# PDB_schem.net
KiCad netlist of a schematic drawn in Altium Designer
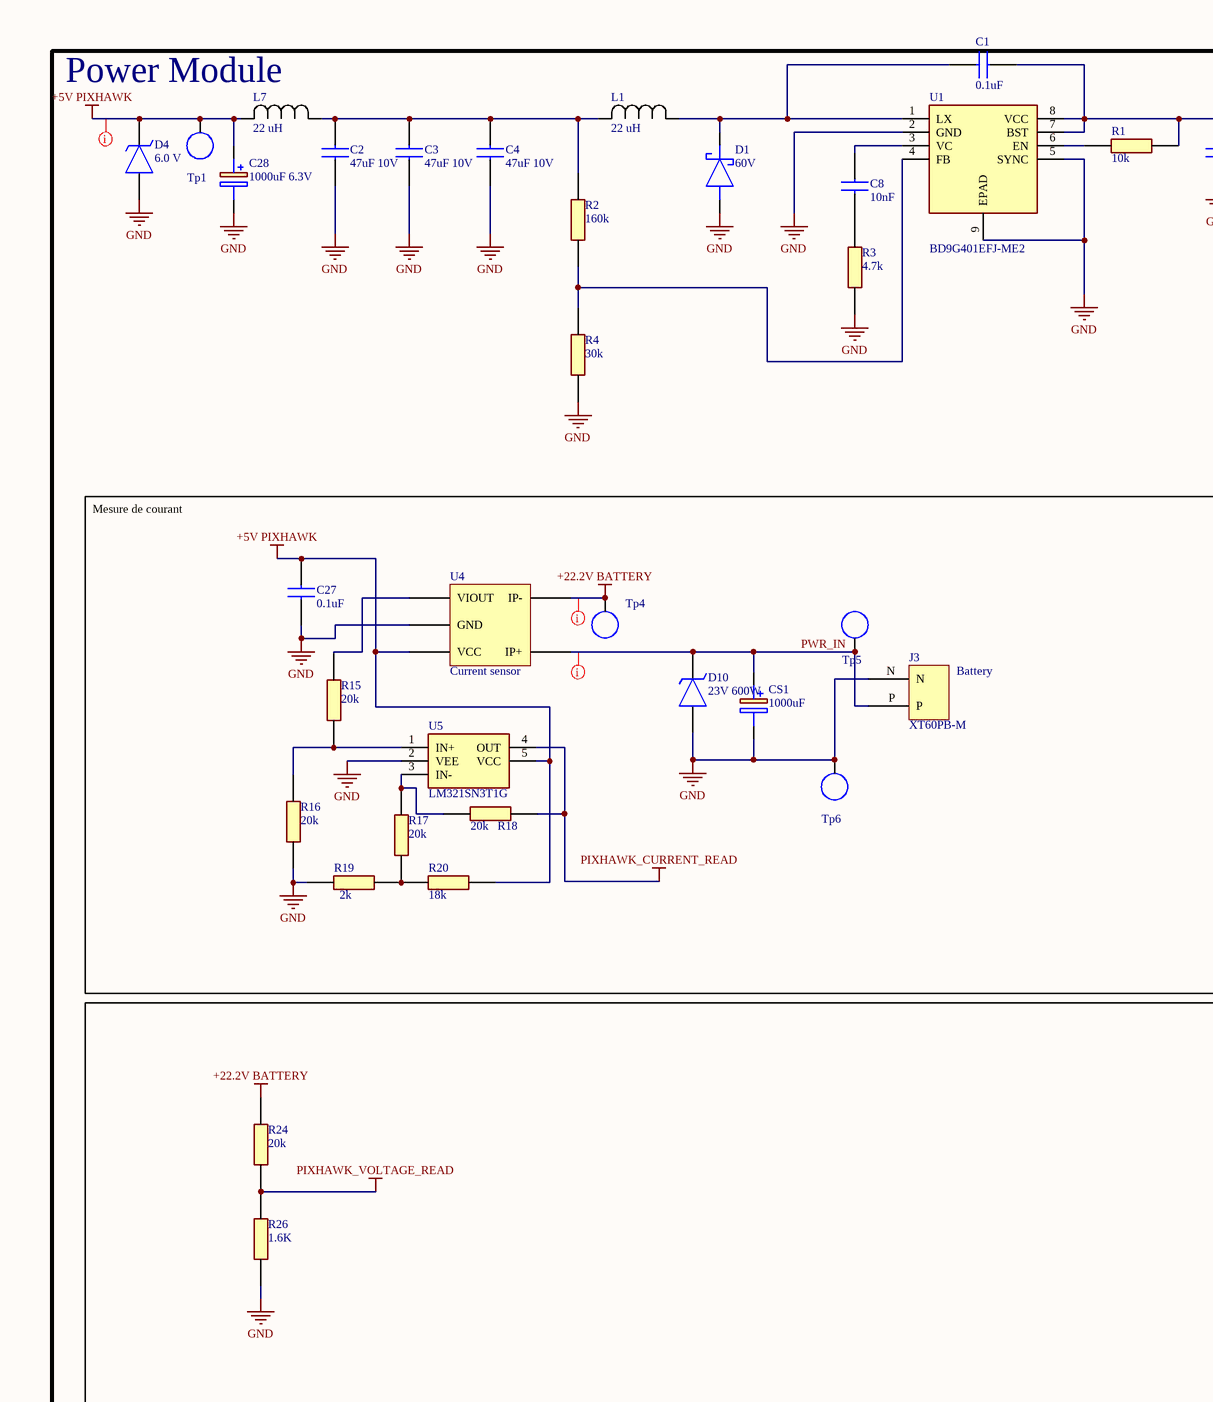
[diagram p0: PDB_schem.SchDoc, left]
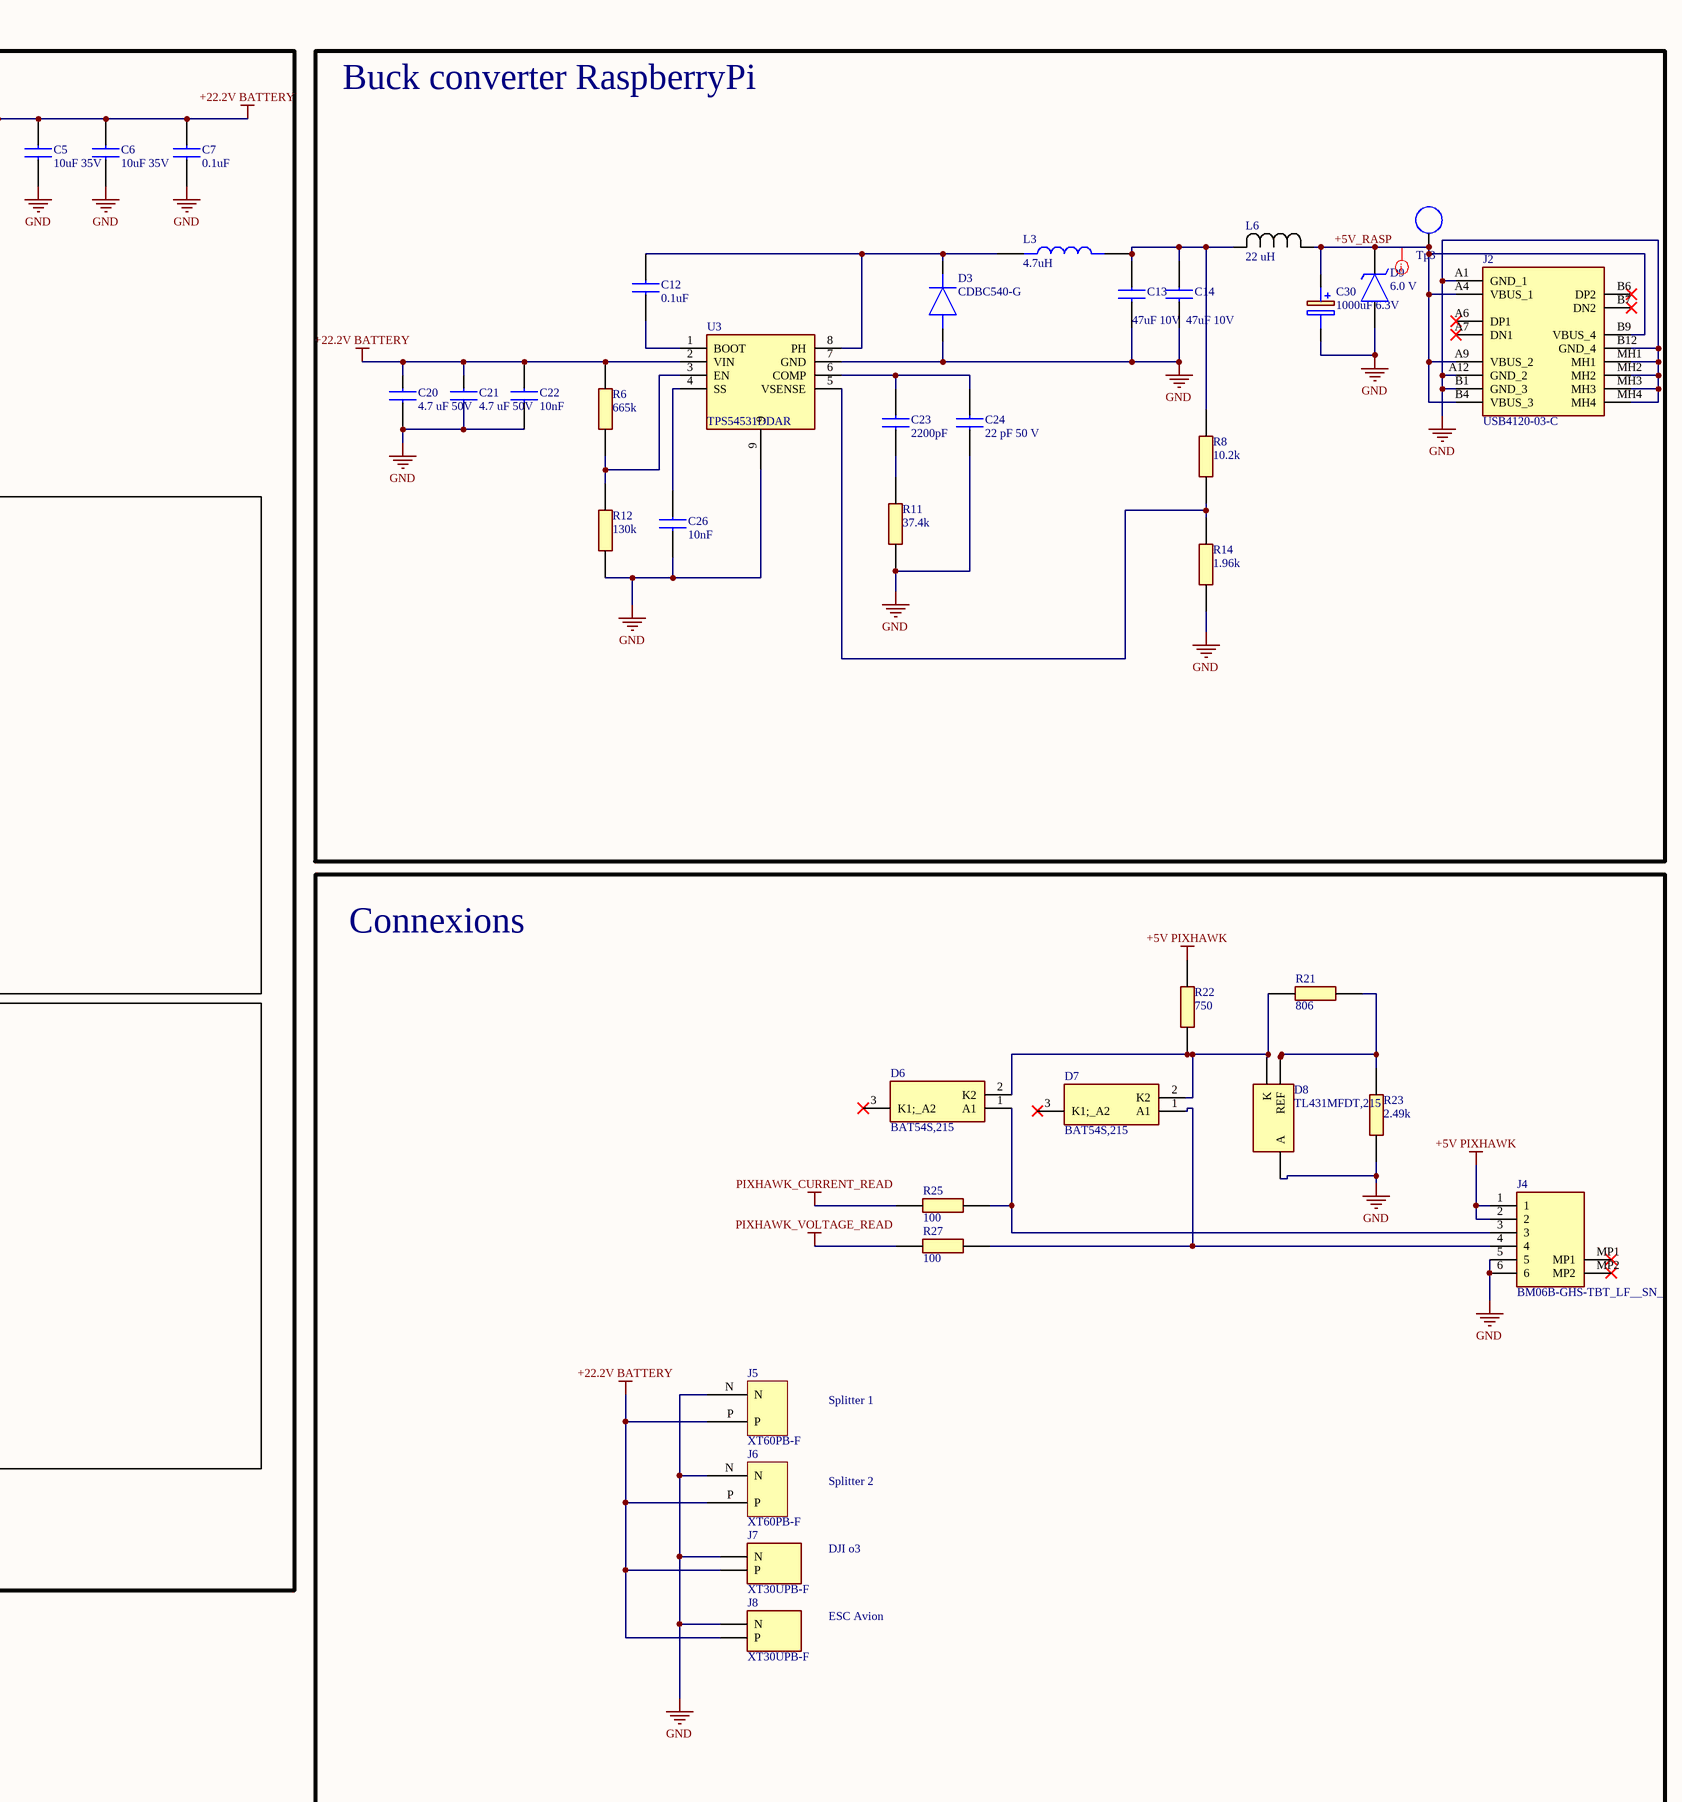
[diagram p1: PDB_schem.SchDoc, middle]
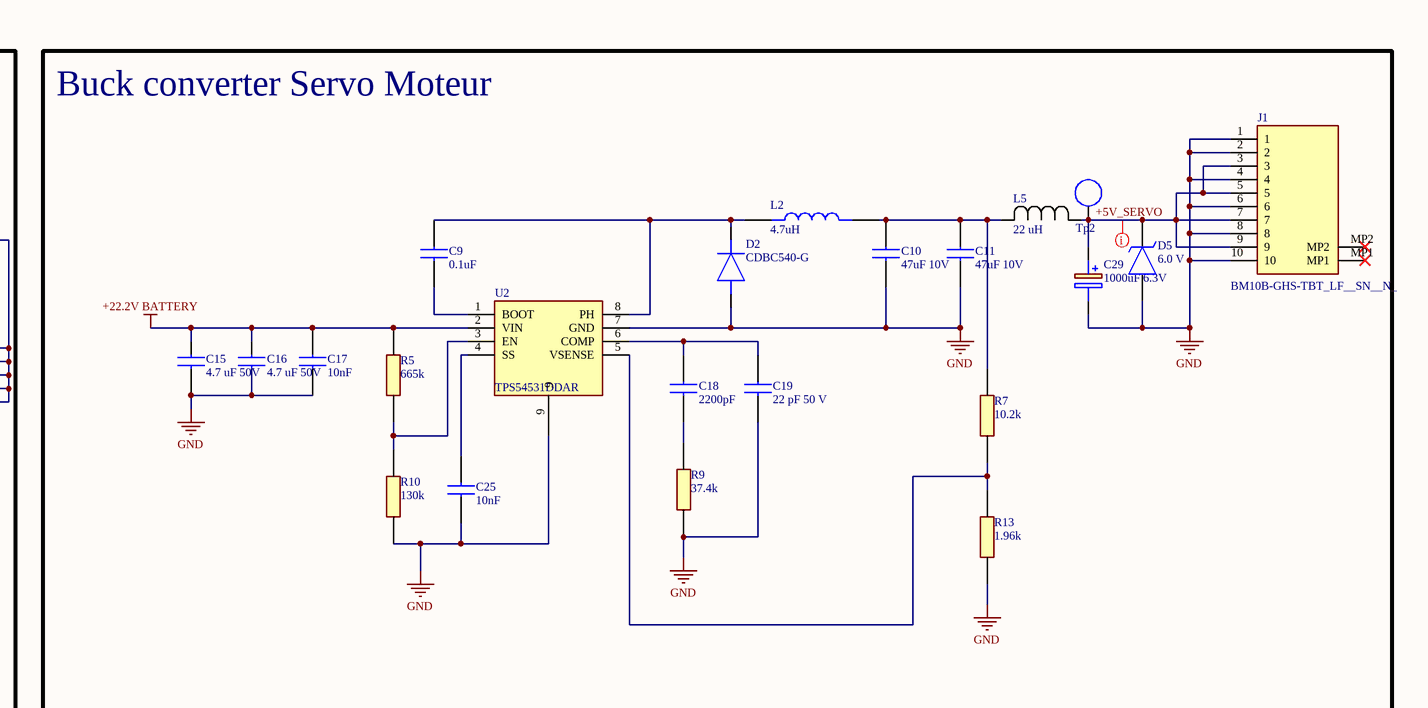
[diagram p2: PDB_schem.SchDoc, right]

(export (version "E")
  (design (tool "Eeschema 10.0.6"))
  (components
    (comp (ref "C1")
      (value "0.1uF")
      (footprint "CAPC2012X145N")
      (description "Capacitor")
      (fields
        (field (name "MANUFACTURER_PART_NUMBER") "C2012X7R2A104K125AA")
        (field (name "MOUSER PART NUMBER") "810-C2012X7R2A104K")
      )
      (libsource (lib "SchLib_PDB_V1") (part "C2012X7R2A104K125AA"))
    )
    (comp (ref "C2")
      (value "47uF 10V")
      (footprint "SamacSys:CAPC2012X145N")
      (description "Capacitor")
      (fields
        (field (name "MANUFACTURER_PART_NUMBER") "C2012X5R1A476M125AC")
        (field (name "MOUSER PART NUMBER") "810-C2012X5R1A476M")
      )
      (libsource (lib "SchLib_PDB_V1") (part "C2012X5R1A476M125AC"))
    )
    (comp (ref "C3")
      (value "47uF 10V")
      (footprint "SamacSys:CAPC2012X145N")
      (description "Capacitor")
      (fields
        (field (name "MANUFACTURER_PART_NUMBER") "C2012X5R1A476M125AC")
        (field (name "MOUSER PART NUMBER") "810-C2012X5R1A476M")
      )
      (libsource (lib "SchLib_PDB_V1") (part "C2012X5R1A476M125AC"))
    )
    (comp (ref "C4")
      (value "47uF 10V")
      (footprint "SamacSys:CAPC2012X145N")
      (description "Capacitor")
      (fields
        (field (name "MANUFACTURER_PART_NUMBER") "C2012X5R1A476M125AC")
        (field (name "MOUSER PART NUMBER") "810-C2012X5R1A476M")
      )
      (libsource (lib "SchLib_PDB_V1") (part "C2012X5R1A476M125AC"))
    )
    (comp (ref "C5")
      (value "10uF 35V")
      (footprint "CAPC2012X145N")
      (description "Capacitor")
      (fields
        (field (name "MANUFACTURER_PART_NUMBER") "C2012X5R1V106K125AC")
        (field (name "MOUSER PART NUMBER") "810-C2012X5R1V106K1C")
      )
      (libsource (lib "SchLib_PDB_V1") (part "C2012X5R1V106K125AC"))
    )
    (comp (ref "C6")
      (value "10uF 35V")
      (footprint "CAPC2012X145N")
      (description "Capacitor")
      (fields
        (field (name "MANUFACTURER_PART_NUMBER") "C2012X5R1V106K125AC")
        (field (name "MOUSER PART NUMBER") "810-C2012X5R1V106K1C")
      )
      (libsource (lib "SchLib_PDB_V1") (part "C2012X5R1V106K125AC"))
    )
    (comp (ref "C7")
      (value "0.1uF")
      (footprint "CAPC2012X145N")
      (description "Capacitor")
      (fields
        (field (name "MANUFACTURER_PART_NUMBER") "C2012X7R2A104K125AA")
        (field (name "MOUSER PART NUMBER") "810-C2012X7R2A104K")
      )
      (libsource (lib "SchLib_PDB_V1") (part "C2012X7R2A104K125AA"))
    )
    (comp (ref "C8")
      (value "10nF")
      (footprint "CAPC2012X145N")
      (description "Capacitor")
      (fields
        (field (name "MANUFACTURER_PART_NUMBER") "C2012X7R2E103K125AA")
        (field (name "MOUSER PART NUMBER") "810-C2012X7R2E103K")
      )
      (libsource (lib "SchLib_PDB_V1") (part "C2012X7R2E103K125AA"))
    )
    (comp (ref "C9")
      (value "0.1uF")
      (footprint "CAPC2012X145N")
      (description "Capacitor")
      (fields
        (field (name "MANUFACTURER_PART_NUMBER") "C2012X7R2A104K125AA")
        (field (name "MOUSER PART NUMBER") "810-C2012X7R2A104K")
      )
      (libsource (lib "SchLib_PDB_V1") (part "C2012X7R2A104K125AA"))
    )
    (comp (ref "C10")
      (value "47uF 10V")
      (footprint "SamacSys:CAPC2012X145N")
      (description "Capacitor")
      (fields
        (field (name "MANUFACTURER_PART_NUMBER") "C2012X5R1A476M125AC")
        (field (name "MOUSER PART NUMBER") "810-C2012X5R1A476M")
      )
      (libsource (lib "SchLib_PDB_V1") (part "C2012X5R1A476M125AC"))
    )
    (comp (ref "C11")
      (value "47uF 10V")
      (footprint "SamacSys:CAPC2012X145N")
      (description "Capacitor")
      (fields
        (field (name "MANUFACTURER_PART_NUMBER") "C2012X5R1A476M125AC")
        (field (name "MOUSER PART NUMBER") "810-C2012X5R1A476M")
      )
      (libsource (lib "SchLib_PDB_V1") (part "C2012X5R1A476M125AC"))
    )
    (comp (ref "C12")
      (value "0.1uF")
      (footprint "CAPC2012X145N")
      (description "Capacitor")
      (fields
        (field (name "MANUFACTURER_PART_NUMBER") "C2012X7R2A104K125AA")
        (field (name "MOUSER PART NUMBER") "810-C2012X7R2A104K")
      )
      (libsource (lib "SchLib_PDB_V1") (part "C2012X7R2A104K125AA"))
    )
    (comp (ref "C13")
      (value "47uF 10V")
      (footprint "SamacSys:CAPC2012X145N")
      (description "Capacitor")
      (fields
        (field (name "MANUFACTURER_PART_NUMBER") "C2012X5R1A476M125AC")
        (field (name "MOUSER PART NUMBER") "810-C2012X5R1A476M")
      )
      (libsource (lib "SchLib_PDB_V1") (part "C2012X5R1A476M125AC"))
    )
    (comp (ref "C14")
      (value "47uF 10V")
      (footprint "SamacSys:CAPC2012X145N")
      (description "Capacitor")
      (fields
        (field (name "MANUFACTURER_PART_NUMBER") "C2012X5R1A476M125AC")
        (field (name "MOUSER PART NUMBER") "810-C2012X5R1A476M")
      )
      (libsource (lib "SchLib_PDB_V1") (part "C2012X5R1A476M125AC"))
    )
    (comp (ref "C15")
      (value "4.7 uF 50V")
      (footprint "CAPC2012X145N")
      (description "Capacitor")
      (fields
        (field (name "MANUFACTURER_PART_NUMBER") "GRM21BR61H475KE51L")
        (field (name "MOUSER PART NUMBER") "81-GRM21BR61H475KE1L")
      )
      (libsource (lib "SchLib_PDB_V1") (part "GRM21BR61H475KE51L"))
    )
    (comp (ref "C16")
      (value "4.7 uF 50V")
      (footprint "CAPC2012X145N")
      (description "Capacitor")
      (fields
        (field (name "MANUFACTURER_PART_NUMBER") "GRM21BR61H475KE51L")
        (field (name "MOUSER PART NUMBER") "81-GRM21BR61H475KE1L")
      )
      (libsource (lib "SchLib_PDB_V1") (part "GRM21BR61H475KE51L"))
    )
    (comp (ref "C17")
      (value "10nF")
      (footprint "CAPC2012X145N")
      (description "Capacitor")
      (fields
        (field (name "MANUFACTURER_PART_NUMBER") "C2012X7R2E103K125AA")
        (field (name "MOUSER PART NUMBER") "810-C2012X7R2E103K")
      )
      (libsource (lib "SchLib_PDB_V1") (part "C2012X7R2E103K125AA"))
    )
    (comp (ref "C18")
      (value "2200pF")
      (footprint "CAPC3216X130N")
      (description "Capacitor 2200pF 630V")
      (fields (field (name "MANUFACTURER_PART_NUMBER") "CGA5H4C0G2J222J115AA"))
      (libsource (lib "SchLib_PDB_V1") (part "CGA5H4C0G2J222J115AA"))
    )
    (comp (ref "C19")
      (value "22 pF 50 V")
      (footprint "CAPC2012X70N")
      (description "Capacitor")
      (fields
        (field (name "MANUFACTURER_PART_NUMBER") "CC0805JRNPO9BN220")
        (field (name "MOUSER PART NUMBER") "603-CC805JRNPO9BN220")
      )
      (libsource (lib "SchLib_PDB_V1") (part "CC0805JRNPO9BN220"))
    )
    (comp (ref "C20")
      (value "4.7 uF 50V")
      (footprint "CAPC2012X145N")
      (description "Capacitor")
      (fields
        (field (name "MANUFACTURER_PART_NUMBER") "GRM21BR61H475KE51L")
        (field (name "MOUSER PART NUMBER") "81-GRM21BR61H475KE1L")
      )
      (libsource (lib "SchLib_PDB_V1") (part "GRM21BR61H475KE51L"))
    )
    (comp (ref "C21")
      (value "4.7 uF 50V")
      (footprint "CAPC2012X145N")
      (description "Capacitor")
      (fields
        (field (name "MANUFACTURER_PART_NUMBER") "GRM21BR61H475KE51L")
        (field (name "MOUSER PART NUMBER") "81-GRM21BR61H475KE1L")
      )
      (libsource (lib "SchLib_PDB_V1") (part "GRM21BR61H475KE51L"))
    )
    (comp (ref "C22")
      (value "10nF")
      (footprint "CAPC2012X145N")
      (description "Capacitor")
      (fields
        (field (name "MANUFACTURER_PART_NUMBER") "C2012X7R2E103K125AA")
        (field (name "MOUSER PART NUMBER") "810-C2012X7R2E103K")
      )
      (libsource (lib "SchLib_PDB_V1") (part "C2012X7R2E103K125AA"))
    )
    (comp (ref "C23")
      (value "2200pF")
      (footprint "CAPC3216X130N")
      (description "Capacitor 2200pF 630V")
      (fields (field (name "MANUFACTURER_PART_NUMBER") "CGA5H4C0G2J222J115AA"))
      (libsource (lib "SchLib_PDB_V1") (part "CGA5H4C0G2J222J115AA"))
    )
    (comp (ref "C24")
      (value "22 pF 50 V")
      (footprint "CAPC2012X70N")
      (description "Capacitor")
      (fields
        (field (name "MANUFACTURER_PART_NUMBER") "CC0805JRNPO9BN220")
        (field (name "MOUSER PART NUMBER") "603-CC805JRNPO9BN220")
      )
      (libsource (lib "SchLib_PDB_V1") (part "CC0805JRNPO9BN220"))
    )
    (comp (ref "C25")
      (value "10nF")
      (footprint "CAPC2012X145N")
      (description "Capacitor")
      (fields
        (field (name "MANUFACTURER_PART_NUMBER") "C2012X7R2E103K125AA")
        (field (name "MOUSER PART NUMBER") "810-C2012X7R2E103K")
      )
      (libsource (lib "SchLib_PDB_V1") (part "C2012X7R2E103K125AA"))
    )
    (comp (ref "C26")
      (value "10nF")
      (footprint "CAPC2012X145N")
      (description "Capacitor")
      (fields
        (field (name "MANUFACTURER_PART_NUMBER") "C2012X7R2E103K125AA")
        (field (name "MOUSER PART NUMBER") "810-C2012X7R2E103K")
      )
      (libsource (lib "SchLib_PDB_V1") (part "C2012X7R2E103K125AA"))
    )
    (comp (ref "C27")
      (value "0.1uF")
      (footprint "CAPC2012X145N")
      (description "Capacitor")
      (fields
        (field (name "MANUFACTURER_PART_NUMBER") "C2012X7R2A104K125AA")
        (field (name "MOUSER PART NUMBER") "810-C2012X7R2A104K")
      )
      (libsource (lib "SchLib_PDB_V1") (part "C2012X7R2A104K125AA"))
    )
    (comp (ref "C28")
      (value "1000uF 6.3V")
      (footprint "CAPAE830X1050N")
      (description "Capacitor Polarised")
      (fields
        (field (name "MANUFACTURER_PART_NUMBER") "UCD0J102MNL1GS")
        (field (name "MOUSER PART NUMBER") "647-UCD0J102MNL1GS")
      )
      (libsource (lib "SchLib_PDB_V1") (part "UCD0J102MNL1GS"))
    )
    (comp (ref "C29")
      (value "1000uF 6.3V")
      (footprint "CAPAE830X1050N")
      (description "Capacitor Polarised")
      (fields
        (field (name "MANUFACTURER_PART_NUMBER") "UCD0J102MNL1GS")
        (field (name "MOUSER PART NUMBER") "647-UCD0J102MNL1GS")
      )
      (libsource (lib "SchLib_PDB_V1") (part "UCD0J102MNL1GS"))
    )
    (comp (ref "C30")
      (value "1000uF 6.3V")
      (footprint "CAPAE830X1050N")
      (description "Capacitor Polarised")
      (fields
        (field (name "MANUFACTURER_PART_NUMBER") "UCD0J102MNL1GS")
        (field (name "MOUSER PART NUMBER") "647-UCD0J102MNL1GS")
      )
      (libsource (lib "SchLib_PDB_V1") (part "UCD0J102MNL1GS"))
    )
    (comp (ref "CS1")
      (value "1000uF")
      (footprint "CAPPRD500W60D1025H2150")
      (description "Capacitor Polarised")
      (fields
        (field (name "MANUFACTURER_PART_NUMBER") "35PX1000MEFC10X20")
        (field (name "MOUSER PART NUMBER") "232-35PX1000MEFC10X2")
      )
      (libsource (lib "SchLib_PDB_V1") (part "35PX1000MEFC10X20"))
    )
    (comp (ref "D1")
      (value "60V")
      (footprint "SODFL4725X105N")
      (description "Schottky Diode")
      (fields
        (field (name "MANUFACTURER_PART_NUMBER") "RBR5LAM60ATFTR")
        (field (name "MOUSER PART NUMBER") "755-RBR5LAM60ATFTR")
      )
      (libsource (lib "SchLib_PDB_V1") (part "RBR5LAM60ATFTR"))
    )
    (comp (ref "D2")
      (value "CDBC540-G")
      (footprint "DIOM8059X290N")
      (description "Diode")
      (fields (field (name "MOUSER PART NUMBER") "750-CDBC540-G"))
      (libsource (lib "SchLib_PDB_V1") (part "CDBC540-G"))
    )
    (comp (ref "D3")
      (value "CDBC540-G")
      (footprint "DIOM8059X290N")
      (description "Diode")
      (fields (field (name "MOUSER PART NUMBER") "750-CDBC540-G"))
      (libsource (lib "SchLib_PDB_V1") (part "CDBC540-G"))
    )
    (comp (ref "D4")
      (value "6.0 V")
      (footprint "SMBJ12A")
      (description "TVS Diode (Uni-directional)")
      (fields (field (name "MANUFACTURER_PART_NUMBER") "SMBJ6.0A"))
      (libsource (lib "SchLib_PDB_V1") (part "SMBJ6.0A"))
    )
    (comp (ref "D5")
      (value "6.0 V")
      (footprint "SMBJ12A")
      (description "TVS Diode (Uni-directional)")
      (fields (field (name "MANUFACTURER_PART_NUMBER") "SMBJ6.0A"))
      (libsource (lib "SchLib_PDB_V1") (part "SMBJ6.0A"))
    )
    (comp (ref "D6")
      (value "BAT54S,215")
      (footprint "SOT95P230X110-3N")
      (description "Schottky Diode")
      (fields (field (name "MOUSER PART NUMBER") "771-BAT54S-T/R"))
      (libsource (lib "SchLib_PDB_V1") (part "BAT54S,215"))
    )
    (comp (ref "D7")
      (value "BAT54S,215")
      (footprint "SOT95P230X110-3N")
      (description "Schottky Diode")
      (fields (field (name "MOUSER PART NUMBER") "771-BAT54S-T/R"))
      (libsource (lib "SchLib_PDB_V1") (part "BAT54S,215"))
    )
    (comp (ref "D8")
      (value "TL431MFDT,215")
      (footprint "SOT95P230X110-3N")
      (description "Integrated Circuit")
      (fields (field (name "MOUSER PART NUMBER") "771-TL431MFDT215"))
      (libsource (lib "SchLib_PDB_V1") (part "TL431MFDT,215"))
    )
    (comp (ref "D9")
      (value "6.0 V")
      (footprint "SMBJ12A")
      (description "TVS Diode (Uni-directional)")
      (fields (field (name "MANUFACTURER_PART_NUMBER") "SMBJ6.0A"))
      (libsource (lib "SchLib_PDB_V1") (part "SMBJ6.0A"))
    )
    (comp (ref "D10")
      (value "23V 600W")
      (footprint "SM6F22AY")
      (description "TVS Diode (Uni-directional)")
      (fields
        (field (name "MANUFACTURER_PART_NUMBER") "SM6F23AY")
        (field (name "MOUSER PART NUMBER") "511-SM6F23AY")
      )
      (libsource (lib "SchLib_PDB_V1") (part "SM6F23AY"))
    )
    (comp (ref "J1")
      (value "BM10B-GHS-TBT_LF__SN__N_")
      (footprint "BM10BGHSTBTLFSNN")
      (description "Connector")
      (fields (field (name "MANUFACTURER_PART_NUMBER") "BM10B-GHS-TBT(LF)(SN)(N)"))
      (libsource (lib "SchLib_PDB_V1") (part "BM10B-GHS-TBT_LF__SN__N_"))
    )
    (comp (ref "J2")
      (value "USB4120-03-C")
      (footprint "USB412003C")
      (description "Connector")
      (fields (field (name "MOUSER PART NUMBER") "640-USB4120-03-C"))
      (libsource (lib "SchLib_PDB_V1") (part "USB4120-03-C"))
    )
    (comp (ref "J3")
      (value "XT60PB-M")
      (footprint "XT60PB-M")
      (description "Connector")
      (libsource (lib "SchLib_PDB_V1") (part "XT60PB-M"))
    )
    (comp (ref "J4")
      (value "BM06B-GHS-TBT_LF__SN_")
      (footprint "BM06BGHSTBTLFSN")
      (description "Connector")
      (fields
        (field (name "MANUFACTURER_PART_NUMBER") "BM06B-GHS-TBT(LF)(SN)")
        (field (name "MOUSER PART NUMBER") "306-BM06BGHSTBTLFSNN")
      )
      (libsource (lib "SchLib_PDB_V1") (part "BM06B-GHS-TBT_LF__SN_"))
    )
    (comp (ref "J5")
      (value "XT60PB-F")
      (footprint "XT60PB-F")
      (description "Connector")
      (libsource (lib "SchLib_PDB_V1") (part "XT60PB-F"))
    )
    (comp (ref "J6")
      (value "XT60PB-F")
      (footprint "XT60PB-F")
      (description "Connector")
      (libsource (lib "SchLib_PDB_V1") (part "XT60PB-F"))
    )
    (comp (ref "J7")
      (value "XT30UPB-F")
      (footprint "XT30UPBF")
      (description "Connector")
      (libsource (lib "SchLib_PDB_V1") (part "XT30UPB-F"))
    )
    (comp (ref "J8")
      (value "XT30UPB-F")
      (footprint "XT30UPBF")
      (description "Connector")
      (libsource (lib "SchLib_PDB_V1") (part "XT30UPB-F"))
    )
    (comp (ref "L1")
      (value "22 uH")
      (footprint "IND_104CDMCCDS_SUM")
      (description "Bobine de 22 uH, 5 A")
      (fields
        (field (name "MANUFACTURER_PART_NUMBER") "104CDMCCDS-220MC")
        (field (name "COPYRIGHT") "Copyright (C) 2025 Ultra Librarian. All rights reserved.")
      )
      (libsource (lib "SchLib_PDB_V1") (part "104CDMCCDS-220MC"))
    )
    (comp (ref "L2")
      (value "4.7uH")
      (footprint "IND_ECS-MPIL0530-4R7MC")
      (description "4.7 µH Shielded Molded Inductor 5 A 60mOhm Max Nonstandard -")
      (fields (field (name "MF") "ECS Inc.") (field (name "MP") "ECS-MPIL0530-4R7MC"))
      (libsource (lib "SchLib_PDB_V1") (part "ECS-MPIL0530-4R7MC"))
    )
    (comp (ref "L3")
      (value "4.7uH")
      (footprint "IND_ECS-MPIL0530-4R7MC")
      (description "4.7 µH Shielded Molded Inductor 5 A 60mOhm Max Nonstandard -")
      (fields (field (name "MF") "ECS Inc.") (field (name "MP") "ECS-MPIL0530-4R7MC"))
      (libsource (lib "SchLib_PDB_V1") (part "ECS-MPIL0530-4R7MC"))
    )
    (comp (ref "L5")
      (value "22 uH")
      (footprint "IND_104CDMCCDS_SUM")
      (description "Bobine de 22 uH, 5 A")
      (fields
        (field (name "MANUFACTURER_PART_NUMBER") "104CDMCCDS-220MC")
        (field (name "COPYRIGHT") "Copyright (C) 2025 Ultra Librarian. All rights reserved.")
      )
      (libsource (lib "SchLib_PDB_V1") (part "104CDMCCDS-220MC"))
    )
    (comp (ref "L6")
      (value "22 uH")
      (footprint "IND_104CDMCCDS_SUM")
      (description "Bobine de 22 uH, 5 A")
      (fields
        (field (name "MANUFACTURER_PART_NUMBER") "104CDMCCDS-220MC")
        (field (name "COPYRIGHT") "Copyright (C) 2025 Ultra Librarian. All rights reserved.")
      )
      (libsource (lib "SchLib_PDB_V1") (part "104CDMCCDS-220MC"))
    )
    (comp (ref "L7")
      (value "22 uH")
      (footprint "IND_104CDMCCDS_SUM")
      (description "Bobine de 22 uH, 5 A")
      (fields
        (field (name "MANUFACTURER_PART_NUMBER") "104CDMCCDS-220MC")
        (field (name "COPYRIGHT") "Copyright (C) 2025 Ultra Librarian. All rights reserved.")
      )
      (libsource (lib "SchLib_PDB_V1") (part "104CDMCCDS-220MC"))
    )
    (comp (ref "R1")
      (value "10k")
      (footprint "RESC2012X60N")
      (description "Resistor")
      (fields
        (field (name "MANUFACTURER_PART_NUMBER") "CRCW080510K0FKEAHP")
        (field (name "MOUSER PART NUMBER") "71-CRCW080510K0FKEAH")
      )
      (libsource (lib "SchLib_PDB_V1") (part "CRCW080510K0FKEAHP"))
    )
    (comp (ref "R2")
      (value "160k")
      (footprint "RESC2012X60N")
      (description "Resistor")
      (fields (field (name "MANUFACTURER_PART_NUMBER") "CRCW0805160KFKEAHP"))
      (libsource (lib "SchLib_PDB_V1") (part "CRCW0805160KFKEAHP"))
    )
    (comp (ref "R3")
      (value "4.7k")
      (footprint "RESC2012X60N")
      (description "Resistor")
      (fields
        (field (name "MANUFACTURER_PART_NUMBER") "CRCW08054K70FKEAC")
        (field (name "MOUSER PART NUMBER") "71-CRCW08054K70FKEAC")
      )
      (libsource (lib "SchLib_PDB_V1") (part "CRCW08054K70FKEAC"))
    )
    (comp (ref "R4")
      (value "30k")
      (footprint "RESC2012X60N")
      (description "Resistor")
      (fields
        (field (name "MANUFACTURER_PART_NUMBER") "CRCW080530K0FKEAC")
        (field (name "MOUSER PART NUMBER") "71-CRCW080530K0FKEAC")
      )
      (libsource (lib "SchLib_PDB_V1") (part "CRCW080530K0FKEAC"))
    )
    (comp (ref "R5")
      (value "665k")
      (footprint "RESC2012X50N")
      (description "Resistor")
      (fields (field (name "MANUFACTURER_PART_NUMBER") "CRCW0805665KFKEA"))
      (libsource (lib "SchLib_PDB_V1") (part "CRCW0805665KFKEA"))
    )
    (comp (ref "R6")
      (value "665k")
      (footprint "RESC2012X50N")
      (description "Resistor")
      (fields (field (name "MANUFACTURER_PART_NUMBER") "CRCW0805665KFKEA"))
      (libsource (lib "SchLib_PDB_V1") (part "CRCW0805665KFKEA"))
    )
    (comp (ref "R7")
      (value "10.2k")
      (footprint "RESC2012X50N")
      (description "Resistor")
      (fields
        (field (name "MANUFACTURER_PART_NUMBER") "CRCW080510K2FKEA")
        (field (name "MOUSER PART NUMBER") "71-CRCW0805-10.2K-E3")
      )
      (libsource (lib "SchLib_PDB_V1") (part "CRCW080510K2FKEA"))
    )
    (comp (ref "R8")
      (value "10.2k")
      (footprint "RESC2012X50N")
      (description "Resistor")
      (fields
        (field (name "MANUFACTURER_PART_NUMBER") "CRCW080510K2FKEA")
        (field (name "MOUSER PART NUMBER") "71-CRCW0805-10.2K-E3")
      )
      (libsource (lib "SchLib_PDB_V1") (part "CRCW080510K2FKEA"))
    )
    (comp (ref "R9")
      (value "37.4k")
      (footprint "RESC2012X50N")
      (description "Resistor")
      (fields
        (field (name "MANUFACTURER_PART_NUMBER") "CRCW080537K4FKEA")
        (field (name "MOUSER PART NUMBER") "71-CRCW0805-37.4K-E3")
      )
      (libsource (lib "SchLib_PDB_V1") (part "CRCW080537K4FKEA"))
    )
    (comp (ref "R10")
      (value "130k")
      (footprint "RESC2012X50N")
      (description "Resistor")
      (fields
        (field (name "MANUFACTURER_PART_NUMBER") "CRCW0805130KFKEA")
        (field (name "MOUSER PART NUMBER") "71-CRCW0805-130K-E3")
      )
      (libsource (lib "SchLib_PDB_V1") (part "CRCW0805130KFKEA"))
    )
    (comp (ref "R11")
      (value "37.4k")
      (footprint "RESC2012X50N")
      (description "Resistor")
      (fields
        (field (name "MANUFACTURER_PART_NUMBER") "CRCW080537K4FKEA")
        (field (name "MOUSER PART NUMBER") "71-CRCW0805-37.4K-E3")
      )
      (libsource (lib "SchLib_PDB_V1") (part "CRCW080537K4FKEA"))
    )
    (comp (ref "R12")
      (value "130k")
      (footprint "RESC2012X50N")
      (description "Resistor")
      (fields
        (field (name "MANUFACTURER_PART_NUMBER") "CRCW0805130KFKEA")
        (field (name "MOUSER PART NUMBER") "71-CRCW0805-130K-E3")
      )
      (libsource (lib "SchLib_PDB_V1") (part "CRCW0805130KFKEA"))
    )
    (comp (ref "R13")
      (value "1.96k")
      (footprint "RESC2012X50N")
      (description "Resistor")
      (fields
        (field (name "MANUFACTURER_PART_NUMBER") "CRCW08051K96FKEA")
        (field (name "MOUSER PART NUMBER") "71-CRCW08051K96FKEA")
      )
      (libsource (lib "SchLib_PDB_V1") (part "CRCW08051K96FKEA"))
    )
    (comp (ref "R14")
      (value "1.96k")
      (footprint "RESC2012X50N")
      (description "Resistor")
      (fields
        (field (name "MANUFACTURER_PART_NUMBER") "CRCW08051K96FKEA")
        (field (name "MOUSER PART NUMBER") "71-CRCW08051K96FKEA")
      )
      (libsource (lib "SchLib_PDB_V1") (part "CRCW08051K96FKEA"))
    )
    (comp (ref "R15")
      (value "20k")
      (footprint "RESC2012X50N")
      (description "Resistor")
      (fields
        (field (name "MANUFACTURER_PART_NUMBER") "CRCW080520K0FKEA")
        (field (name "MOUSER PART NUMBER") "71-CRCW0805-20K-E3")
      )
      (libsource (lib "") (part "CRCW080520K0FKEA_2"))
    )
    (comp (ref "R16")
      (value "20k")
      (footprint "RESC2012X50N")
      (description "Resistor")
      (fields
        (field (name "MANUFACTURER_PART_NUMBER") "CRCW080520K0FKEA")
        (field (name "MOUSER PART NUMBER") "71-CRCW0805-20K-E3")
      )
      (libsource (lib "") (part "CRCW080520K0FKEA_2"))
    )
    (comp (ref "R17")
      (value "20k")
      (footprint "RESC2012X50N")
      (description "Resistor")
      (fields
        (field (name "MANUFACTURER_PART_NUMBER") "CRCW080520K0FKEA")
        (field (name "MOUSER PART NUMBER") "71-CRCW0805-20K-E3")
      )
      (libsource (lib "") (part "CRCW080520K0FKEA_2"))
    )
    (comp (ref "R18")
      (value "20k")
      (footprint "RESC2012X50N")
      (description "Resistor")
      (fields
        (field (name "MANUFACTURER_PART_NUMBER") "CRCW080520K0FKEA")
        (field (name "MOUSER PART NUMBER") "71-CRCW0805-20K-E3")
      )
      (libsource (lib "") (part "CRCW080520K0FKEA_1"))
    )
    (comp (ref "R19")
      (value "2k")
      (footprint "RESC2012X60N")
      (description "Resistor")
      (fields
        (field (name "MANUFACTURER_PART_NUMBER") "CRCW08052K00FKEAC")
        (field (name "MOUSER PART NUMBER") "71-CRCW08052K00FKEAC")
      )
      (libsource (lib "SchLib_PDB_V1") (part "CRCW08052K00FKEAC"))
    )
    (comp (ref "R20")
      (value "18k")
      (footprint "RESC2012X50N")
      (description "Resistor")
      (fields
        (field (name "MANUFACTURER_PART_NUMBER") "CRCW080518K0FKEAC")
        (field (name "MOUSER PART NUMBER") "71-CRCW080518K0FKEAC")
      )
      (libsource (lib "SchLib_PDB_V1") (part "CRCW080518K0FKEAC"))
    )
    (comp (ref "R21")
      (value "806")
      (footprint "RESC2012X60N")
      (description "Resistor")
      (fields (field (name "MANUFACTURER_PART_NUMBER") "CRCW0805806RFKEAHP"))
      (libsource (lib "SchLib_PDB_V1") (part "CRCW0805806RFKEAHP"))
    )
    (comp (ref "R22")
      (value "750")
      (footprint "RESC2012X60N")
      (description "Resistor")
      (fields
        (field (name "MANUFACTURER_PART_NUMBER") "CRCW0805750RFKEAHP")
        (field (name "MOUSER PART NUMBER") "71-CRCW0805750RFKEAH")
      )
      (libsource (lib "SchLib_PDB_V1") (part "CRCW0805750RFKEAHP"))
    )
    (comp (ref "R23")
      (value "2.49k")
      (footprint "RESC2012X50N")
      (description "Resistor")
      (fields
        (field (name "MANUFACTURER_PART_NUMBER") "CRCW08052K49FKEAC")
        (field (name "MOUSER PART NUMBER") "71-CRCW08052K49FKEAC")
      )
      (libsource (lib "SchLib_PDB_V1") (part "CRCW08052K49FKEAC"))
    )
    (comp (ref "R24")
      (value "20k")
      (footprint "RESC2012X50N")
      (description "Resistor")
      (fields
        (field (name "MANUFACTURER_PART_NUMBER") "CRCW080520K0FKEA")
        (field (name "MOUSER PART NUMBER") "71-CRCW0805-20K-E3")
      )
      (libsource (lib "SchLib_PDB_V1") (part "CRCW080520K0FKEA"))
    )
    (comp (ref "R25")
      (value "100")
      (footprint "RESC2012X50N")
      (description "Resistor")
      (fields
        (field (name "MANUFACTURER_PART_NUMBER") "CRCW0805100RFKEA")
        (field (name "MOUSER PART NUMBER") "71-CRCW0805-100-E3")
      )
      (libsource (lib "SchLib_PDB_V1") (part "CRCW0805100RFKEA"))
    )
    (comp (ref "R26")
      (value "1.6K")
      (footprint "RESC2012X60N")
      (description "Resistor")
      (fields
        (field (name "MANUFACTURER_PART_NUMBER") "CRCW08051K60FKEAC")
        (field (name "MOUSER PART NUMBER") "71-CRCW08051K60FKEAC")
      )
      (libsource (lib "SchLib_PDB_V1") (part "CRCW08051K60FKEAC"))
    )
    (comp (ref "R27")
      (value "100")
      (footprint "RESC2012X50N")
      (description "Resistor")
      (fields
        (field (name "MANUFACTURER_PART_NUMBER") "CRCW0805100RFKEA")
        (field (name "MOUSER PART NUMBER") "71-CRCW0805-100-E3")
      )
      (libsource (lib "SchLib_PDB_V1") (part "CRCW0805100RFKEA"))
    )
    (comp (ref "Tp1")
      (value "Testpoint")
      (footprint "Testpoint")
      (libsource (lib "SchLib_PDB_V1") (part "Testpoint"))
    )
    (comp (ref "Tp2")
      (value "Testpoint")
      (footprint "Testpoint")
      (libsource (lib "SchLib_PDB_V1") (part "Testpoint"))
    )
    (comp (ref "Tp3")
      (value "Testpoint")
      (footprint "Testpoint")
      (libsource (lib "SchLib_PDB_V1") (part "Testpoint"))
    )
    (comp (ref "Tp4")
      (value "Testpoint")
      (footprint "Testpoint")
      (libsource (lib "SchLib_PDB_V1") (part "Testpoint"))
    )
    (comp (ref "Tp5")
      (value "Testpoint")
      (footprint "Testpoint")
      (libsource (lib "SchLib_PDB_V1") (part "Testpoint"))
    )
    (comp (ref "Tp6")
      (value "Testpoint")
      (footprint "Testpoint")
      (libsource (lib "SchLib_PDB_V1") (part "Testpoint"))
    )
    (comp (ref "U1")
      (value "BD9G401EFJ-ME2")
      (footprint "SOIC127P600X100-9N")
      (description "Buck converter")
      (fields (field (name "MOUSER PART NUMBER") "755-BD9G401EFJ-ME2"))
      (libsource (lib "SchLib_PDB_V1") (part "BD9G401EFJ-ME2"))
    )
    (comp (ref "U2")
      (value "TPS54531DDAR")
      (footprint "SOIC127P600X175-8N")
      (description "Power Supply")
      (fields (field (name "MOUSER PART NUMBER") "595-TPS54531DDAR"))
      (libsource (lib "SchLib_PDB_V1") (part "TPS54531DDAR"))
    )
    (comp (ref "U3")
      (value "TPS54531DDAR")
      (footprint "SOIC127P600X175-8N")
      (description "Power Supply")
      (fields (field (name "MOUSER PART NUMBER") "595-TPS54531DDAR"))
      (libsource (lib "SchLib_PDB_V1") (part "TPS54531DDAR"))
    )
    (comp (ref "U4")
      (value "Current sensor")
      (footprint "ACS770xCB-PFF - Sans Via-in-Pad")
      (description "150 A , Unidirectional")
      (libsource (lib "SchLib_PDB_V1") (part "ACS770KCB-150U-PFF-T"))
    )
    (comp (ref "U5")
      (value "LM321SN3T1G")
      (footprint "SOT95P275X110-5N")
      (description "Integrated Circuit")
      (fields (field (name "MOUSER PART NUMBER") "863-LM321SN3T1G"))
      (libsource (lib "SchLib_PDB_V1") (part "LM321SN3T1G"))
    )
  )
  (nets
    (net (code "1") (name "+5V PIXHAWK") (class "Default")
      (node (ref "C27") (pin "2") (pinfunction "2_2") (pintype "passive"))
      (node (ref "C28") (pin "1") (pinfunction "+_1") (pintype "passive"))
      (node (ref "D4") (pin "1") (pinfunction "K_1") (pintype "passive"))
      (node (ref "J4") (pin "1") (pinfunction "1_1") (pintype "passive"))
      (node (ref "J4") (pin "2") (pinfunction "2_2") (pintype "passive"))
      (node (ref "L7") (pin "2") (pinfunction "2_2") (pintype "passive"))
      (node (ref "R20") (pin "2") (pinfunction "2_2") (pintype "passive"))
      (node (ref "R22") (pin "2") (pinfunction "2_2") (pintype "passive"))
      (node (ref "Tp1") (pin "TP") (pinfunction "TP_TP") (pintype "passive"))
      (node (ref "U4") (pin "1") (pinfunction "VCC_1") (pintype "passive"))
      (node (ref "U5") (pin "5") (pinfunction "VCC_5") (pintype "passive"))
    )
    (net (code "2") (name "+22.2V BATTERY") (class "Default")
      (node (ref "C1") (pin "2") (pinfunction "2_2") (pintype "passive"))
      (node (ref "C15") (pin "2") (pinfunction "2_2") (pintype "passive"))
      (node (ref "C16") (pin "2") (pinfunction "2_2") (pintype "passive"))
      (node (ref "C17") (pin "2") (pinfunction "2_2") (pintype "passive"))
      (node (ref "C20") (pin "2") (pinfunction "2_2") (pintype "passive"))
      (node (ref "C21") (pin "2") (pinfunction "2_2") (pintype "passive"))
      (node (ref "C22") (pin "2") (pinfunction "2_2") (pintype "passive"))
      (node (ref "C5") (pin "2") (pinfunction "2_2") (pintype "passive"))
      (node (ref "C6") (pin "2") (pinfunction "2_2") (pintype "passive"))
      (node (ref "C7") (pin "2") (pinfunction "2_2") (pintype "passive"))
      (node (ref "J5") (pin "P") (pinfunction "P_P") (pintype "passive"))
      (node (ref "J6") (pin "P") (pinfunction "P_P") (pintype "passive"))
      (node (ref "J7") (pin "1") (pinfunction "P_1") (pintype "passive"))
      (node (ref "J8") (pin "1") (pinfunction "P_1") (pintype "passive"))
      (node (ref "R1") (pin "2") (pinfunction "2_2") (pintype "passive"))
      (node (ref "R24") (pin "1") (pinfunction "1_1") (pintype "passive"))
      (node (ref "R5") (pin "2") (pinfunction "2_2") (pintype "passive"))
      (node (ref "R6") (pin "2") (pinfunction "2_2") (pintype "passive"))
      (node (ref "Tp4") (pin "TP") (pinfunction "TP_TP") (pintype "passive"))
      (node (ref "U1") (pin "7") (pinfunction "BST_7") (pintype "passive"))
      (node (ref "U1") (pin "8") (pinfunction "VCC_8") (pintype "passive"))
      (node (ref "U2") (pin "2") (pinfunction "VIN_2") (pintype "passive"))
      (node (ref "U3") (pin "2") (pinfunction "VIN_2") (pintype "passive"))
      (node (ref "U4") (pin "5") (pinfunction "IP-_5") (pintype "passive"))
    )
    (net (code "3") (name "/+5V_RASP") (class "Default")
      (node (ref "C30") (pin "1") (pinfunction "+_1") (pintype "passive"))
      (node (ref "D9") (pin "1") (pinfunction "K_1") (pintype "passive"))
      (node (ref "J2") (pin "A4") (pinfunction "VBUS_1_A4") (pintype "passive"))
      (node (ref "J2") (pin "A9") (pinfunction "VBUS_2_A9") (pintype "passive"))
      (node (ref "J2") (pin "B4") (pinfunction "VBUS_3_B4") (pintype "passive"))
      (node (ref "J2") (pin "B9") (pinfunction "VBUS_4_B9") (pintype "passive"))
      (node (ref "L6") (pin "1") (pinfunction "1_1") (pintype "passive"))
      (node (ref "Tp3") (pin "TP") (pinfunction "TP_TP") (pintype "passive"))
    )
    (net (code "4") (name "/+5V_SERVO") (class "Default")
      (node (ref "C29") (pin "1") (pinfunction "+_1") (pintype "passive"))
      (node (ref "D5") (pin "1") (pinfunction "K_1") (pintype "passive"))
      (node (ref "J1") (pin "3") (pinfunction "3_3") (pintype "passive"))
      (node (ref "J1") (pin "5") (pinfunction "5_5") (pintype "passive"))
      (node (ref "J1") (pin "7") (pinfunction "7_7") (pintype "passive"))
      (node (ref "J1") (pin "9") (pinfunction "9_9") (pintype "passive"))
      (node (ref "L5") (pin "1") (pinfunction "1_1") (pintype "passive"))
      (node (ref "Tp2") (pin "TP") (pinfunction "TP_TP") (pintype "passive"))
    )
    (net (code "5") (name "/PWR_IN") (class "Default")
      (node (ref "CS1") (pin "1") (pinfunction "+_1") (pintype "passive"))
      (node (ref "D10") (pin "1") (pinfunction "K_1") (pintype "passive"))
      (node (ref "J3") (pin "P") (pinfunction "P_P") (pintype "passive"))
      (node (ref "Tp5") (pin "TP") (pinfunction "TP_TP") (pintype "passive"))
      (node (ref "U4") (pin "4") (pinfunction "IP+_4") (pintype "passive"))
    )
    (net (code "6") (name "GND") (class "Default")
      (node (ref "C10") (pin "1") (pinfunction "1_1") (pintype "passive"))
      (node (ref "C11") (pin "1") (pinfunction "1_1") (pintype "passive"))
      (node (ref "C13") (pin "1") (pinfunction "1_1") (pintype "passive"))
      (node (ref "C14") (pin "1") (pinfunction "1_1") (pintype "passive"))
      (node (ref "C15") (pin "1") (pinfunction "1_1") (pintype "passive"))
      (node (ref "C16") (pin "1") (pinfunction "1_1") (pintype "passive"))
      (node (ref "C17") (pin "1") (pinfunction "1_1") (pintype "passive"))
      (node (ref "C19") (pin "1") (pinfunction "1_1") (pintype "passive"))
      (node (ref "C2") (pin "1") (pinfunction "1_1") (pintype "passive"))
      (node (ref "C20") (pin "1") (pinfunction "1_1") (pintype "passive"))
      (node (ref "C21") (pin "1") (pinfunction "1_1") (pintype "passive"))
      (node (ref "C22") (pin "1") (pinfunction "1_1") (pintype "passive"))
      (node (ref "C24") (pin "1") (pinfunction "1_1") (pintype "passive"))
      (node (ref "C25") (pin "1") (pinfunction "1_1") (pintype "passive"))
      (node (ref "C26") (pin "1") (pinfunction "1_1") (pintype "passive"))
      (node (ref "C27") (pin "1") (pinfunction "1_1") (pintype "passive"))
      (node (ref "C28") (pin "2") (pinfunction "-_2") (pintype "passive"))
      (node (ref "C29") (pin "2") (pinfunction "-_2") (pintype "passive"))
      (node (ref "C3") (pin "1") (pinfunction "1_1") (pintype "passive"))
      (node (ref "C30") (pin "2") (pinfunction "-_2") (pintype "passive"))
      (node (ref "C4") (pin "1") (pinfunction "1_1") (pintype "passive"))
      (node (ref "C5") (pin "1") (pinfunction "1_1") (pintype "passive"))
      (node (ref "C6") (pin "1") (pinfunction "1_1") (pintype "passive"))
      (node (ref "C7") (pin "1") (pinfunction "1_1") (pintype "passive"))
      (node (ref "CS1") (pin "2") (pinfunction "-_2") (pintype "passive"))
      (node (ref "D1") (pin "2") (pinfunction "A_2") (pintype "passive"))
      (node (ref "D10") (pin "2") (pinfunction "A_2") (pintype "passive"))
      (node (ref "D2") (pin "2") (pinfunction "A_2") (pintype "passive"))
      (node (ref "D3") (pin "2") (pinfunction "A_2") (pintype "passive"))
      (node (ref "D4") (pin "2") (pinfunction "A_2") (pintype "passive"))
      (node (ref "D5") (pin "2") (pinfunction "A_2") (pintype "passive"))
      (node (ref "D8") (pin "3") (pinfunction "A_3") (pintype "passive"))
      (node (ref "D9") (pin "2") (pinfunction "A_2") (pintype "passive"))
      (node (ref "J1") (pin "1") (pinfunction "1_1") (pintype "passive"))
      (node (ref "J1") (pin "10") (pinfunction "10_10") (pintype "passive"))
      (node (ref "J1") (pin "2") (pinfunction "2_2") (pintype "passive"))
      (node (ref "J1") (pin "4") (pinfunction "4_4") (pintype "passive"))
      (node (ref "J1") (pin "6") (pinfunction "6_6") (pintype "passive"))
      (node (ref "J1") (pin "8") (pinfunction "8_8") (pintype "passive"))
      (node (ref "J2") (pin "A1") (pinfunction "GND_1_A1") (pintype "passive"))
      (node (ref "J2") (pin "A12") (pinfunction "GND_2_A12") (pintype "passive"))
      (node (ref "J2") (pin "B1") (pinfunction "GND_3_B1") (pintype "passive"))
      (node (ref "J2") (pin "B12") (pinfunction "GND_4_B12") (pintype "passive"))
      (node (ref "J2") (pin "MH1") (pinfunction "MH1_MH1") (pintype "passive"))
      (node (ref "J2") (pin "MH2") (pinfunction "MH2_MH2") (pintype "passive"))
      (node (ref "J2") (pin "MH3") (pinfunction "MH3_MH3") (pintype "passive"))
      (node (ref "J2") (pin "MH4") (pinfunction "MH4_MH4") (pintype "passive"))
      (node (ref "J3") (pin "N") (pinfunction "N_N") (pintype "passive"))
      (node (ref "J4") (pin "5") (pinfunction "5_5") (pintype "passive"))
      (node (ref "J4") (pin "6") (pinfunction "6_6") (pintype "passive"))
      (node (ref "J5") (pin "N") (pinfunction "N_N") (pintype "passive"))
      (node (ref "J6") (pin "N") (pinfunction "N_N") (pintype "passive"))
      (node (ref "J7") (pin "2") (pinfunction "N_2") (pintype "passive"))
      (node (ref "J8") (pin "2") (pinfunction "N_2") (pintype "passive"))
      (node (ref "R10") (pin "1") (pinfunction "1_1") (pintype "passive"))
      (node (ref "R11") (pin "1") (pinfunction "1_1") (pintype "passive"))
      (node (ref "R12") (pin "1") (pinfunction "1_1") (pintype "passive"))
      (node (ref "R13") (pin "1") (pinfunction "1_1") (pintype "passive"))
      (node (ref "R14") (pin "1") (pinfunction "1_1") (pintype "passive"))
      (node (ref "R16") (pin "1") (pinfunction "1_1") (pintype "passive"))
      (node (ref "R19") (pin "1") (pinfunction "1_1") (pintype "passive"))
      (node (ref "R23") (pin "1") (pinfunction "1_1") (pintype "passive"))
      (node (ref "R26") (pin "1") (pinfunction "1_1") (pintype "passive"))
      (node (ref "R3") (pin "1") (pinfunction "1_1") (pintype "passive"))
      (node (ref "R4") (pin "1") (pinfunction "1_1") (pintype "passive"))
      (node (ref "R9") (pin "1") (pinfunction "1_1") (pintype "passive"))
      (node (ref "Tp6") (pin "TP") (pinfunction "TP_TP") (pintype "passive"))
      (node (ref "U1") (pin "2") (pinfunction "GND_2") (pintype "passive"))
      (node (ref "U1") (pin "5") (pinfunction "SYNC_5") (pintype "passive"))
      (node (ref "U1") (pin "9") (pinfunction "EPAD_9") (pintype "passive"))
      (node (ref "U2") (pin "7") (pinfunction "GND_7") (pintype "passive"))
      (node (ref "U2") (pin "9") (pinfunction "9_9") (pintype "passive"))
      (node (ref "U3") (pin "7") (pinfunction "GND_7") (pintype "passive"))
      (node (ref "U3") (pin "9") (pinfunction "9_9") (pintype "passive"))
      (node (ref "U4") (pin "2") (pinfunction "GND_2") (pintype "passive"))
      (node (ref "U5") (pin "2") (pinfunction "VEE_2") (pintype "passive"))
    )
    (net (code "7") (name "Net-(C2-Pad2)") (class "Default")
      (node (ref "C2") (pin "2") (pinfunction "2_2") (pintype "passive"))
      (node (ref "C3") (pin "2") (pinfunction "2_2") (pintype "passive"))
      (node (ref "C4") (pin "2") (pinfunction "2_2") (pintype "passive"))
      (node (ref "L1") (pin "2") (pinfunction "2_2") (pintype "passive"))
      (node (ref "L7") (pin "1") (pinfunction "1_1") (pintype "passive"))
      (node (ref "R2") (pin "2") (pinfunction "2_2") (pintype "passive"))
    )
    (net (code "8") (name "Net-(C8-Pad1)") (class "Default")
      (node (ref "C8") (pin "1") (pinfunction "1_1") (pintype "passive"))
      (node (ref "R3") (pin "2") (pinfunction "2_2") (pintype "passive"))
    )
    (net (code "9") (name "Net-(C10-Pad2)") (class "Default")
      (node (ref "C10") (pin "2") (pinfunction "2_2") (pintype "passive"))
      (node (ref "C11") (pin "2") (pinfunction "2_2") (pintype "passive"))
      (node (ref "L2") (pin "2") (pinfunction "2_2") (pintype "passive"))
      (node (ref "L5") (pin "2") (pinfunction "2_2") (pintype "passive"))
      (node (ref "R7") (pin "2") (pinfunction "2_2") (pintype "passive"))
    )
    (net (code "10") (name "Net-(C13-Pad2)") (class "Default")
      (node (ref "C13") (pin "2") (pinfunction "2_2") (pintype "passive"))
      (node (ref "C14") (pin "2") (pinfunction "2_2") (pintype "passive"))
      (node (ref "L3") (pin "2") (pinfunction "2_2") (pintype "passive"))
      (node (ref "L6") (pin "2") (pinfunction "2_2") (pintype "passive"))
      (node (ref "R8") (pin "2") (pinfunction "2_2") (pintype "passive"))
    )
    (net (code "11") (name "Net-(C18-Pad1)") (class "Default")
      (node (ref "C18") (pin "1") (pinfunction "1_1") (pintype "passive"))
      (node (ref "R9") (pin "2") (pinfunction "2_2") (pintype "passive"))
    )
    (net (code "12") (name "Net-(C23-Pad1)") (class "Default")
      (node (ref "C23") (pin "1") (pinfunction "1_1") (pintype "passive"))
      (node (ref "R11") (pin "2") (pinfunction "2_2") (pintype "passive"))
    )
    (net (code "13") (name "Net-(D1-K)") (class "Default")
      (node (ref "C1") (pin "1") (pinfunction "1_1") (pintype "passive"))
      (node (ref "D1") (pin "1") (pinfunction "K_1") (pintype "passive"))
      (node (ref "L1") (pin "1") (pinfunction "1_1") (pintype "passive"))
      (node (ref "U1") (pin "1") (pinfunction "LX_1") (pintype "passive"))
    )
    (net (code "14") (name "Net-(D2-K)") (class "Default")
      (node (ref "C9") (pin "2") (pinfunction "2_2") (pintype "passive"))
      (node (ref "D2") (pin "1") (pinfunction "K_1") (pintype "passive"))
      (node (ref "L2") (pin "1") (pinfunction "1_1") (pintype "passive"))
      (node (ref "U2") (pin "8") (pinfunction "PH_8") (pintype "passive"))
    )
    (net (code "15") (name "Net-(D3-K)") (class "Default")
      (node (ref "C12") (pin "2") (pinfunction "2_2") (pintype "passive"))
      (node (ref "D3") (pin "1") (pinfunction "K_1") (pintype "passive"))
      (node (ref "L3") (pin "1") (pinfunction "1_1") (pintype "passive"))
      (node (ref "U3") (pin "8") (pinfunction "PH_8") (pintype "passive"))
    )
    (net (code "16") (name "Net-(D6-A1)") (class "Default")
      (node (ref "D6") (pin "1") (pinfunction "A1_1") (pintype "passive"))
      (node (ref "J4") (pin "3") (pinfunction "3_3") (pintype "passive"))
      (node (ref "R25") (pin "2") (pinfunction "2_2") (pintype "passive"))
    )
    (net (code "17") (name "Net-(D6-K2)") (class "Default")
      (node (ref "D6") (pin "2") (pinfunction "K2_2") (pintype "passive"))
      (node (ref "D7") (pin "2") (pinfunction "K2_2") (pintype "passive"))
      (node (ref "D8") (pin "2") (pinfunction "K_2") (pintype "passive"))
      (node (ref "R21") (pin "2") (pinfunction "2_2") (pintype "passive"))
      (node (ref "R22") (pin "1") (pinfunction "1_1") (pintype "passive"))
    )
    (net (code "18") (name "Net-(D7-A1)") (class "Default")
      (node (ref "D7") (pin "1") (pinfunction "A1_1") (pintype "passive"))
      (node (ref "J4") (pin "4") (pinfunction "4_4") (pintype "passive"))
      (node (ref "R27") (pin "2") (pinfunction "2_2") (pintype "passive"))
    )
    (net (code "19") (name "Net-(D8-REF)") (class "Default")
      (node (ref "D8") (pin "1") (pinfunction "REF_1") (pintype "passive"))
      (node (ref "R21") (pin "1") (pinfunction "1_1") (pintype "passive"))
      (node (ref "R23") (pin "2") (pinfunction "2_2") (pintype "passive"))
    )
    (net (code "20") (name "Net-(R17-Pad1)") (class "Default")
      (node (ref "R17") (pin "1") (pinfunction "1_1") (pintype "passive"))
      (node (ref "R19") (pin "2") (pinfunction "2_2") (pintype "passive"))
      (node (ref "R20") (pin "1") (pinfunction "1_1") (pintype "passive"))
    )
    (net (code "21") (name "Net-(U1-EN)") (class "Default")
      (node (ref "R1") (pin "1") (pinfunction "1_1") (pintype "passive"))
      (node (ref "U1") (pin "6") (pinfunction "EN_6") (pintype "passive"))
    )
    (net (code "22") (name "Net-(U1-FB)") (class "Default")
      (node (ref "R2") (pin "1") (pinfunction "1_1") (pintype "passive"))
      (node (ref "R4") (pin "2") (pinfunction "2_2") (pintype "passive"))
      (node (ref "U1") (pin "4") (pinfunction "FB_4") (pintype "passive"))
    )
    (net (code "23") (name "Net-(U1-VC)") (class "Default")
      (node (ref "C8") (pin "2") (pinfunction "2_2") (pintype "passive"))
      (node (ref "U1") (pin "3") (pinfunction "VC_3") (pintype "passive"))
    )
    (net (code "24") (name "Net-(U2-BOOT)") (class "Default")
      (node (ref "C9") (pin "1") (pinfunction "1_1") (pintype "passive"))
      (node (ref "U2") (pin "1") (pinfunction "BOOT_1") (pintype "passive"))
    )
    (net (code "25") (name "Net-(U2-COMP)") (class "Default")
      (node (ref "C18") (pin "2") (pinfunction "2_2") (pintype "passive"))
      (node (ref "C19") (pin "2") (pinfunction "2_2") (pintype "passive"))
      (node (ref "U2") (pin "6") (pinfunction "COMP_6") (pintype "passive"))
    )
    (net (code "26") (name "Net-(U2-EN)") (class "Default")
      (node (ref "R10") (pin "2") (pinfunction "2_2") (pintype "passive"))
      (node (ref "R5") (pin "1") (pinfunction "1_1") (pintype "passive"))
      (node (ref "U2") (pin "3") (pinfunction "EN_3") (pintype "passive"))
    )
    (net (code "27") (name "Net-(U2-SS)") (class "Default")
      (node (ref "C25") (pin "2") (pinfunction "2_2") (pintype "passive"))
      (node (ref "U2") (pin "4") (pinfunction "SS_4") (pintype "passive"))
    )
    (net (code "28") (name "Net-(U2-VSENSE)") (class "Default")
      (node (ref "R13") (pin "2") (pinfunction "2_2") (pintype "passive"))
      (node (ref "R7") (pin "1") (pinfunction "1_1") (pintype "passive"))
      (node (ref "U2") (pin "5") (pinfunction "VSENSE_5") (pintype "passive"))
    )
    (net (code "29") (name "Net-(U3-BOOT)") (class "Default")
      (node (ref "C12") (pin "1") (pinfunction "1_1") (pintype "passive"))
      (node (ref "U3") (pin "1") (pinfunction "BOOT_1") (pintype "passive"))
    )
    (net (code "30") (name "Net-(U3-COMP)") (class "Default")
      (node (ref "C23") (pin "2") (pinfunction "2_2") (pintype "passive"))
      (node (ref "C24") (pin "2") (pinfunction "2_2") (pintype "passive"))
      (node (ref "U3") (pin "6") (pinfunction "COMP_6") (pintype "passive"))
    )
    (net (code "31") (name "Net-(U3-EN)") (class "Default")
      (node (ref "R12") (pin "2") (pinfunction "2_2") (pintype "passive"))
      (node (ref "R6") (pin "1") (pinfunction "1_1") (pintype "passive"))
      (node (ref "U3") (pin "3") (pinfunction "EN_3") (pintype "passive"))
    )
    (net (code "32") (name "Net-(U3-SS)") (class "Default")
      (node (ref "C26") (pin "2") (pinfunction "2_2") (pintype "passive"))
      (node (ref "U3") (pin "4") (pinfunction "SS_4") (pintype "passive"))
    )
    (net (code "33") (name "Net-(U3-VSENSE)") (class "Default")
      (node (ref "R14") (pin "2") (pinfunction "2_2") (pintype "passive"))
      (node (ref "R8") (pin "1") (pinfunction "1_1") (pintype "passive"))
      (node (ref "U3") (pin "5") (pinfunction "VSENSE_5") (pintype "passive"))
    )
    (net (code "34") (name "Net-(U4-VIOUT)") (class "Default")
      (node (ref "R15") (pin "2") (pinfunction "2_2") (pintype "passive"))
      (node (ref "U4") (pin "3") (pinfunction "VIOUT_3") (pintype "passive"))
    )
    (net (code "35") (name "Net-(U5-IN+)") (class "Default")
      (node (ref "R15") (pin "1") (pinfunction "1_1") (pintype "passive"))
      (node (ref "R16") (pin "2") (pinfunction "2_2") (pintype "passive"))
      (node (ref "U5") (pin "1") (pinfunction "IN+_1") (pintype "passive"))
    )
    (net (code "36") (name "Net-(U5-IN-)") (class "Default")
      (node (ref "R17") (pin "2") (pinfunction "2_2") (pintype "passive"))
      (node (ref "R18") (pin "2") (pinfunction "2_2") (pintype "passive"))
      (node (ref "U5") (pin "3") (pinfunction "IN-_3") (pintype "passive"))
    )
    (net (code "37") (name "PIXHAWK_CURRENT_READ") (class "Default")
      (node (ref "R18") (pin "1") (pinfunction "1_1") (pintype "passive"))
      (node (ref "R25") (pin "1") (pinfunction "1_1") (pintype "passive"))
      (node (ref "U5") (pin "4") (pinfunction "OUT_4") (pintype "passive"))
    )
    (net (code "38") (name "PIXHAWK_VOLTAGE_READ") (class "Default")
      (node (ref "R24") (pin "2") (pinfunction "2_2") (pintype "passive"))
      (node (ref "R26") (pin "2") (pinfunction "2_2") (pintype "passive"))
      (node (ref "R27") (pin "1") (pinfunction "1_1") (pintype "passive"))
    )
    (net (code "39") (name "unconnected-(D6-K1;_A2-Pad3)") (class "Default")
      (node (ref "D6") (pin "3") (pinfunction "K1;_A2_3") (pintype "passive+no_connect"))
    )
    (net (code "40") (name "unconnected-(D7-K1;_A2-Pad3)") (class "Default")
      (node (ref "D7") (pin "3") (pinfunction "K1;_A2_3") (pintype "passive+no_connect"))
    )
    (net (code "41") (name "unconnected-(J1-PadMP1)") (class "Default")
      (node (ref "J1") (pin "MP1") (pinfunction "MP1_MP1") (pintype "passive+no_connect"))
    )
    (net (code "42") (name "unconnected-(J1-PadMP2)") (class "Default")
      (node (ref "J1") (pin "MP2") (pinfunction "MP2_MP2") (pintype "passive+no_connect"))
    )
    (net (code "43") (name "unconnected-(J2-DN1-PadA7)") (class "Default")
      (node (ref "J2") (pin "A7") (pinfunction "DN1_A7") (pintype "passive+no_connect"))
    )
    (net (code "44") (name "unconnected-(J2-DN2-PadB7)") (class "Default")
      (node (ref "J2") (pin "B7") (pinfunction "DN2_B7") (pintype "passive+no_connect"))
    )
    (net (code "45") (name "unconnected-(J2-DP1-PadA6)") (class "Default")
      (node (ref "J2") (pin "A6") (pinfunction "DP1_A6") (pintype "passive+no_connect"))
    )
    (net (code "46") (name "unconnected-(J2-DP2-PadB6)") (class "Default")
      (node (ref "J2") (pin "B6") (pinfunction "DP2_B6") (pintype "passive+no_connect"))
    )
    (net (code "47") (name "unconnected-(J4-PadMP1)") (class "Default")
      (node (ref "J4") (pin "MP1") (pinfunction "MP1_MP1") (pintype "passive+no_connect"))
    )
    (net (code "48") (name "unconnected-(J4-PadMP2)") (class "Default")
      (node (ref "J4") (pin "MP2") (pinfunction "MP2_MP2") (pintype "passive+no_connect"))
    )
  )
)
